# RK3566_CSI.net
KiCad netlist of a schematic drawn in Altium Designer
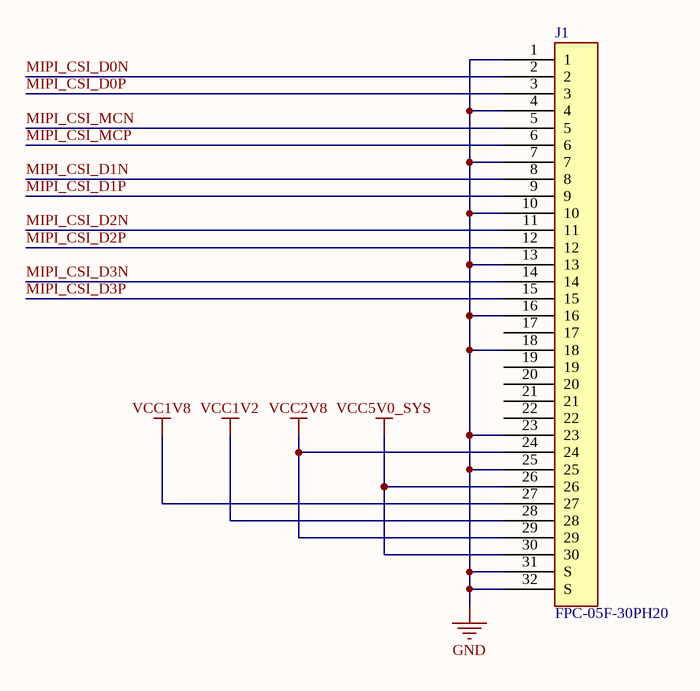
[diagram p0: RK3566_CSI.SchDoc]

(export (version "E")
  (design (tool "Eeschema 10.0.6"))
  (components
    (comp (ref "J1")
      (value "FPC-05F-30PH20")
      (libsource (lib "PersonalAltiumLibrary") (part "FPC-05F-30PH20"))
    )
  )
  (nets
    (net (code "1") (name "/MIPI_CSI_D0N") (class "Default")
      (node (ref "J1") (pin "2") (pinfunction "2_2") (pintype "passive"))
    )
    (net (code "2") (name "/MIPI_CSI_D0P") (class "Default")
      (node (ref "J1") (pin "3") (pinfunction "3_3") (pintype "passive"))
    )
    (net (code "3") (name "/MIPI_CSI_D1N") (class "Default")
      (node (ref "J1") (pin "8") (pinfunction "8_8") (pintype "passive"))
    )
    (net (code "4") (name "/MIPI_CSI_D1P") (class "Default")
      (node (ref "J1") (pin "9") (pinfunction "9_9") (pintype "passive"))
    )
    (net (code "5") (name "/MIPI_CSI_D2N") (class "Default")
      (node (ref "J1") (pin "11") (pinfunction "11_11") (pintype "passive"))
    )
    (net (code "6") (name "/MIPI_CSI_D2P") (class "Default")
      (node (ref "J1") (pin "12") (pinfunction "12_12") (pintype "passive"))
    )
    (net (code "7") (name "/MIPI_CSI_D3N") (class "Default")
      (node (ref "J1") (pin "14") (pinfunction "14_14") (pintype "passive"))
    )
    (net (code "8") (name "/MIPI_CSI_D3P") (class "Default")
      (node (ref "J1") (pin "15") (pinfunction "15_15") (pintype "passive"))
    )
    (net (code "9") (name "/MIPI_CSI_MCN") (class "Default")
      (node (ref "J1") (pin "5") (pinfunction "5_5") (pintype "passive"))
    )
    (net (code "10") (name "/MIPI_CSI_MCP") (class "Default")
      (node (ref "J1") (pin "6") (pinfunction "6_6") (pintype "passive"))
    )
    (net (code "11") (name "GND") (class "Default")
      (node (ref "J1") (pin "1") (pinfunction "1_1") (pintype "passive"))
      (node (ref "J1") (pin "10") (pinfunction "10_10") (pintype "passive"))
      (node (ref "J1") (pin "13") (pinfunction "13_13") (pintype "passive"))
      (node (ref "J1") (pin "16") (pinfunction "16_16") (pintype "passive"))
      (node (ref "J1") (pin "18") (pinfunction "18_18") (pintype "passive"))
      (node (ref "J1") (pin "23") (pinfunction "23_23") (pintype "passive"))
      (node (ref "J1") (pin "25") (pinfunction "25_25") (pintype "passive"))
      (node (ref "J1") (pin "31") (pinfunction "S_31") (pintype "passive"))
      (node (ref "J1") (pin "32") (pinfunction "S_32") (pintype "passive"))
      (node (ref "J1") (pin "4") (pinfunction "4_4") (pintype "passive"))
      (node (ref "J1") (pin "7") (pinfunction "7_7") (pintype "passive"))
    )
    (net (code "12") (name "VCC1V2") (class "Default")
      (node (ref "J1") (pin "28") (pinfunction "28_28") (pintype "passive"))
    )
    (net (code "13") (name "VCC1V8") (class "Default")
      (node (ref "J1") (pin "27") (pinfunction "27_27") (pintype "passive"))
    )
    (net (code "14") (name "VCC2V8") (class "Default")
      (node (ref "J1") (pin "24") (pinfunction "24_24") (pintype "passive"))
      (node (ref "J1") (pin "29") (pinfunction "29_29") (pintype "passive"))
    )
    (net (code "15") (name "VCC5V0_SYS") (class "Default")
      (node (ref "J1") (pin "26") (pinfunction "26_26") (pintype "passive"))
      (node (ref "J1") (pin "30") (pinfunction "30_30") (pintype "passive"))
    )
    (net (code "16") (name "unconnected-(J1-Pad17)") (class "Default")
      (node (ref "J1") (pin "17") (pinfunction "17_17") (pintype "passive"))
    )
    (net (code "17") (name "unconnected-(J1-Pad19)") (class "Default")
      (node (ref "J1") (pin "19") (pinfunction "19_19") (pintype "passive"))
    )
    (net (code "18") (name "unconnected-(J1-Pad20)") (class "Default")
      (node (ref "J1") (pin "20") (pinfunction "20_20") (pintype "passive"))
    )
    (net (code "19") (name "unconnected-(J1-Pad21)") (class "Default")
      (node (ref "J1") (pin "21") (pinfunction "21_21") (pintype "passive"))
    )
    (net (code "20") (name "unconnected-(J1-Pad22)") (class "Default")
      (node (ref "J1") (pin "22") (pinfunction "22_22") (pintype "passive"))
    )
  )
)
